# Buspirate_Main.net
KiCad netlist of a schematic drawn in EasyEDA Pro
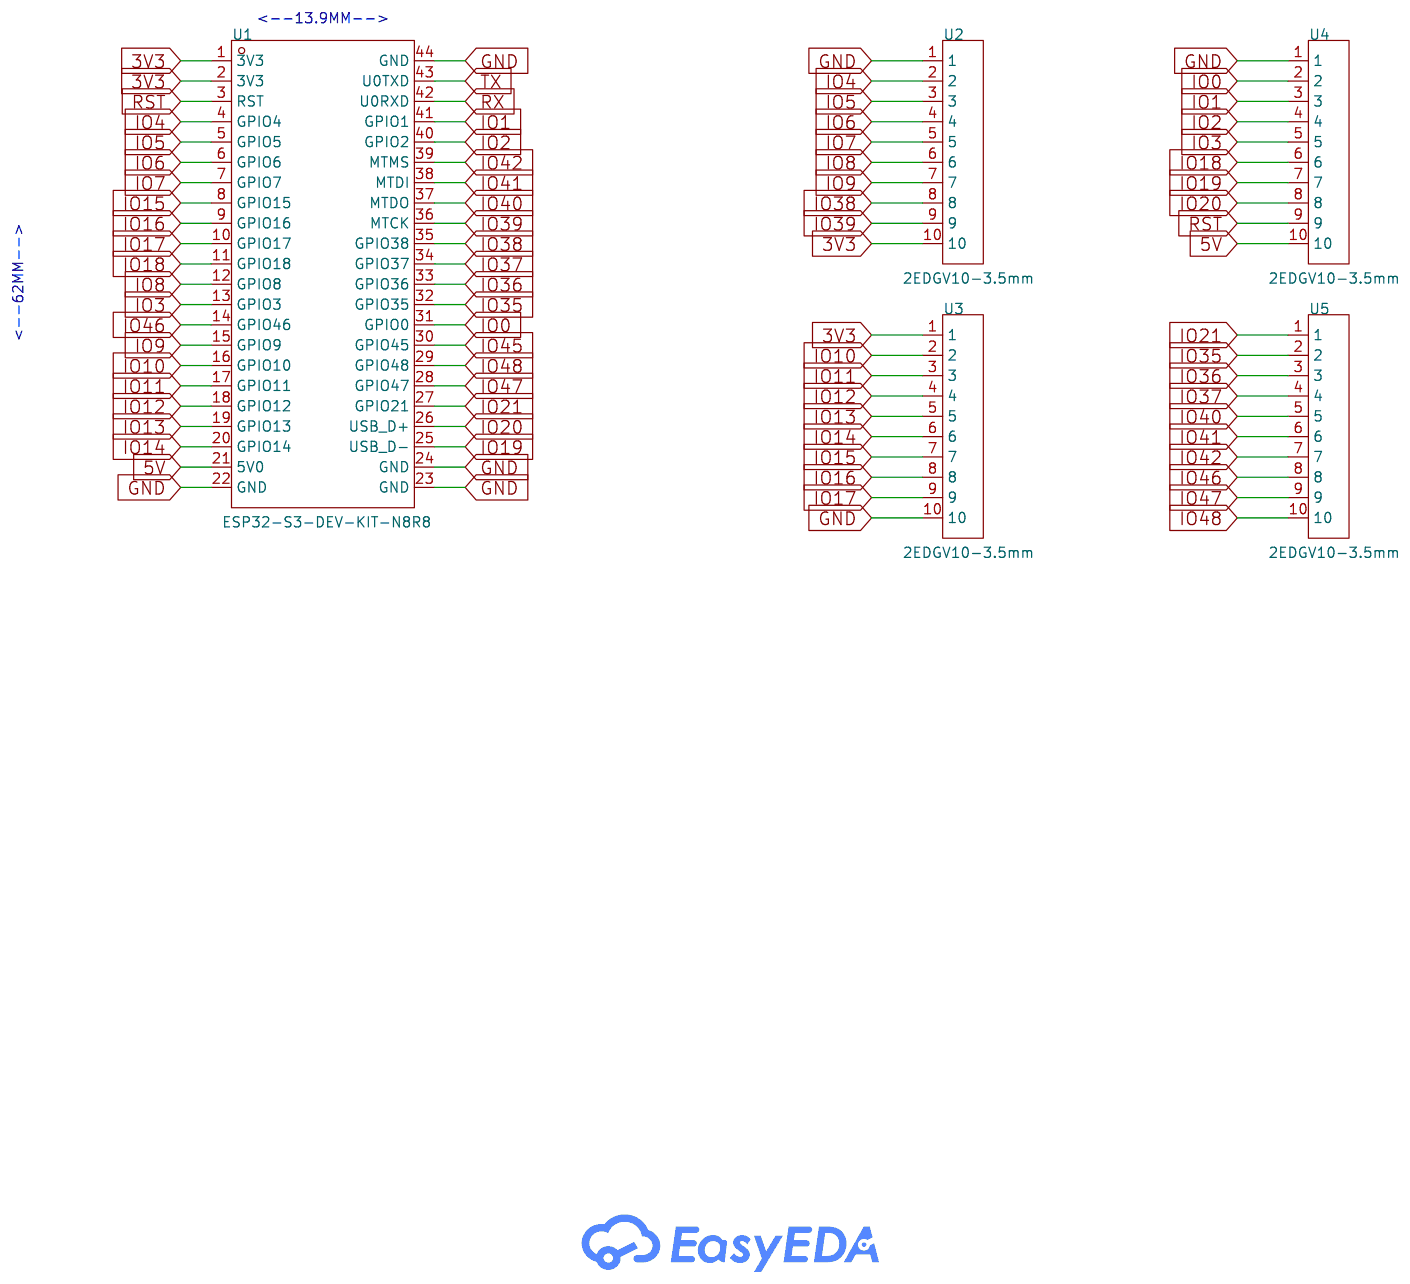
[diagram p0: schematic sheet]

(export (version "E")
  (design (tool "Eeschema 10.0.6"))
  (components
    (comp (ref "U1")
      (value "ESP32-S3-DEV-KIT-N8R8")
      (footprint "easyedapro:COMM-TH_L63.3-W25.4-P2.54-LS22.86")
      (libsource (lib "easyedapro") (part "ESP32-S3-DEV-KIT-N8R8"))
    )
    (comp (ref "U2")
      (value "2EDGV10-3.5mm")
      (footprint "easyedapro:CONN-TH_10P-P3.50")
      (libsource (lib "easyedapro") (part "CONN-TH_10P-P3.50"))
    )
    (comp (ref "U3")
      (value "2EDGV10-3.5mm")
      (footprint "easyedapro:CONN-TH_10P-P3.50")
      (libsource (lib "easyedapro") (part "CONN-TH_10P-P3.50"))
    )
    (comp (ref "U4")
      (value "2EDGV10-3.5mm")
      (footprint "easyedapro:CONN-TH_10P-P3.50")
      (libsource (lib "easyedapro") (part "CONN-TH_10P-P3.50"))
    )
    (comp (ref "U5")
      (value "2EDGV10-3.5mm")
      (footprint "easyedapro:CONN-TH_10P-P3.50")
      (libsource (lib "easyedapro") (part "CONN-TH_10P-P3.50"))
    )
  )
  (nets
    (net (code "1") (name "3V3") (class "Default")
      (node (ref "U1") (pin "1") (pinfunction "3V3_1") (pintype "unspecified"))
      (node (ref "U1") (pin "2") (pinfunction "3V3_2") (pintype "unspecified"))
      (node (ref "U2") (pin "10") (pinfunction "10_10") (pintype "unspecified"))
      (node (ref "U3") (pin "1") (pinfunction "1_1") (pintype "unspecified"))
    )
    (net (code "2") (name "5V") (class "Default")
      (node (ref "U1") (pin "21") (pinfunction "5V0_21") (pintype "unspecified"))
      (node (ref "U4") (pin "10") (pinfunction "10_10") (pintype "unspecified"))
    )
    (net (code "3") (name "GND") (class "Default")
      (node (ref "U1") (pin "22") (pinfunction "GND_22") (pintype "unspecified"))
      (node (ref "U1") (pin "23") (pinfunction "GND_23") (pintype "unspecified"))
      (node (ref "U1") (pin "24") (pinfunction "GND_24") (pintype "unspecified"))
      (node (ref "U1") (pin "44") (pinfunction "GND_44") (pintype "unspecified"))
      (node (ref "U2") (pin "1") (pinfunction "1_1") (pintype "unspecified"))
      (node (ref "U3") (pin "10") (pinfunction "10_10") (pintype "unspecified"))
      (node (ref "U4") (pin "1") (pinfunction "1_1") (pintype "unspecified"))
    )
    (net (code "4") (name "IO0") (class "Default")
      (node (ref "U1") (pin "31") (pinfunction "GPIO0_31") (pintype "unspecified"))
      (node (ref "U4") (pin "2") (pinfunction "2_2") (pintype "unspecified"))
    )
    (net (code "5") (name "IO1") (class "Default")
      (node (ref "U1") (pin "41") (pinfunction "GPIO1_41") (pintype "unspecified"))
      (node (ref "U4") (pin "3") (pinfunction "3_3") (pintype "unspecified"))
    )
    (net (code "6") (name "IO2") (class "Default")
      (node (ref "U1") (pin "40") (pinfunction "GPIO2_40") (pintype "unspecified"))
      (node (ref "U4") (pin "4") (pinfunction "4_4") (pintype "unspecified"))
    )
    (net (code "7") (name "IO3") (class "Default")
      (node (ref "U1") (pin "13") (pinfunction "GPIO3_13") (pintype "unspecified"))
      (node (ref "U4") (pin "5") (pinfunction "5_5") (pintype "unspecified"))
    )
    (net (code "8") (name "IO4") (class "Default")
      (node (ref "U1") (pin "4") (pinfunction "GPIO4_4") (pintype "unspecified"))
      (node (ref "U2") (pin "2") (pinfunction "2_2") (pintype "unspecified"))
    )
    (net (code "9") (name "IO5") (class "Default")
      (node (ref "U1") (pin "5") (pinfunction "GPIO5_5") (pintype "unspecified"))
      (node (ref "U2") (pin "3") (pinfunction "3_3") (pintype "unspecified"))
    )
    (net (code "10") (name "IO6") (class "Default")
      (node (ref "U1") (pin "6") (pinfunction "GPIO6_6") (pintype "unspecified"))
      (node (ref "U2") (pin "4") (pinfunction "4_4") (pintype "unspecified"))
    )
    (net (code "11") (name "IO7") (class "Default")
      (node (ref "U1") (pin "7") (pinfunction "GPIO7_7") (pintype "unspecified"))
      (node (ref "U2") (pin "5") (pinfunction "5_5") (pintype "unspecified"))
    )
    (net (code "12") (name "IO8") (class "Default")
      (node (ref "U1") (pin "12") (pinfunction "GPIO8_12") (pintype "unspecified"))
      (node (ref "U2") (pin "6") (pinfunction "6_6") (pintype "unspecified"))
    )
    (net (code "13") (name "IO9") (class "Default")
      (node (ref "U1") (pin "15") (pinfunction "GPIO9_15") (pintype "unspecified"))
      (node (ref "U2") (pin "7") (pinfunction "7_7") (pintype "unspecified"))
    )
    (net (code "14") (name "IO10") (class "Default")
      (node (ref "U1") (pin "16") (pinfunction "GPIO10_16") (pintype "unspecified"))
      (node (ref "U3") (pin "2") (pinfunction "2_2") (pintype "unspecified"))
    )
    (net (code "15") (name "IO11") (class "Default")
      (node (ref "U1") (pin "17") (pinfunction "GPIO11_17") (pintype "unspecified"))
      (node (ref "U3") (pin "3") (pinfunction "3_3") (pintype "unspecified"))
    )
    (net (code "16") (name "IO12") (class "Default")
      (node (ref "U1") (pin "18") (pinfunction "GPIO12_18") (pintype "unspecified"))
      (node (ref "U3") (pin "4") (pinfunction "4_4") (pintype "unspecified"))
    )
    (net (code "17") (name "IO13") (class "Default")
      (node (ref "U1") (pin "19") (pinfunction "GPIO13_19") (pintype "unspecified"))
      (node (ref "U3") (pin "5") (pinfunction "5_5") (pintype "unspecified"))
    )
    (net (code "18") (name "IO14") (class "Default")
      (node (ref "U1") (pin "20") (pinfunction "GPIO14_20") (pintype "unspecified"))
      (node (ref "U3") (pin "6") (pinfunction "6_6") (pintype "unspecified"))
    )
    (net (code "19") (name "IO15") (class "Default")
      (node (ref "U1") (pin "8") (pinfunction "GPIO15_8") (pintype "unspecified"))
      (node (ref "U3") (pin "7") (pinfunction "7_7") (pintype "unspecified"))
    )
    (net (code "20") (name "IO16") (class "Default")
      (node (ref "U1") (pin "9") (pinfunction "GPIO16_9") (pintype "unspecified"))
      (node (ref "U3") (pin "8") (pinfunction "8_8") (pintype "unspecified"))
    )
    (net (code "21") (name "IO17") (class "Default")
      (node (ref "U1") (pin "10") (pinfunction "GPIO17_10") (pintype "unspecified"))
      (node (ref "U3") (pin "9") (pinfunction "9_9") (pintype "unspecified"))
    )
    (net (code "22") (name "IO18") (class "Default")
      (node (ref "U1") (pin "11") (pinfunction "GPIO18_11") (pintype "unspecified"))
      (node (ref "U4") (pin "6") (pinfunction "6_6") (pintype "unspecified"))
    )
    (net (code "23") (name "IO19") (class "Default")
      (node (ref "U1") (pin "25") (pinfunction "USB_D-_25") (pintype "unspecified"))
      (node (ref "U4") (pin "7") (pinfunction "7_7") (pintype "unspecified"))
    )
    (net (code "24") (name "IO20") (class "Default")
      (node (ref "U1") (pin "26") (pinfunction "USB_D+_26") (pintype "unspecified"))
      (node (ref "U4") (pin "8") (pinfunction "8_8") (pintype "unspecified"))
    )
    (net (code "25") (name "IO21") (class "Default")
      (node (ref "U1") (pin "27") (pinfunction "GPIO21_27") (pintype "unspecified"))
      (node (ref "U5") (pin "1") (pinfunction "1_1") (pintype "unspecified"))
    )
    (net (code "26") (name "IO35") (class "Default")
      (node (ref "U1") (pin "32") (pinfunction "GPIO35_32") (pintype "unspecified"))
      (node (ref "U5") (pin "2") (pinfunction "2_2") (pintype "unspecified"))
    )
    (net (code "27") (name "IO36") (class "Default")
      (node (ref "U1") (pin "33") (pinfunction "GPIO36_33") (pintype "unspecified"))
      (node (ref "U5") (pin "3") (pinfunction "3_3") (pintype "unspecified"))
    )
    (net (code "28") (name "IO37") (class "Default")
      (node (ref "U1") (pin "34") (pinfunction "GPIO37_34") (pintype "unspecified"))
      (node (ref "U5") (pin "4") (pinfunction "4_4") (pintype "unspecified"))
    )
    (net (code "29") (name "IO38") (class "Default")
      (node (ref "U1") (pin "35") (pinfunction "GPIO38_35") (pintype "unspecified"))
      (node (ref "U2") (pin "8") (pinfunction "8_8") (pintype "unspecified"))
    )
    (net (code "30") (name "IO39") (class "Default")
      (node (ref "U1") (pin "36") (pinfunction "MTCK_36") (pintype "unspecified"))
      (node (ref "U2") (pin "9") (pinfunction "9_9") (pintype "unspecified"))
    )
    (net (code "31") (name "IO40") (class "Default")
      (node (ref "U1") (pin "37") (pinfunction "MTDO_37") (pintype "unspecified"))
      (node (ref "U5") (pin "5") (pinfunction "5_5") (pintype "unspecified"))
    )
    (net (code "32") (name "IO41") (class "Default")
      (node (ref "U1") (pin "38") (pinfunction "MTDI_38") (pintype "unspecified"))
      (node (ref "U5") (pin "6") (pinfunction "6_6") (pintype "unspecified"))
    )
    (net (code "33") (name "IO42") (class "Default")
      (node (ref "U1") (pin "39") (pinfunction "MTMS_39") (pintype "unspecified"))
      (node (ref "U5") (pin "7") (pinfunction "7_7") (pintype "unspecified"))
    )
    (net (code "34") (name "IO45") (class "Default")
      (node (ref "U1") (pin "30") (pinfunction "GPIO45_30") (pintype "unspecified"))
    )
    (net (code "35") (name "IO46") (class "Default")
      (node (ref "U1") (pin "14") (pinfunction "GPIO46_14") (pintype "unspecified"))
      (node (ref "U5") (pin "8") (pinfunction "8_8") (pintype "unspecified"))
    )
    (net (code "36") (name "IO47") (class "Default")
      (node (ref "U1") (pin "28") (pinfunction "GPIO47_28") (pintype "unspecified"))
      (node (ref "U5") (pin "9") (pinfunction "9_9") (pintype "unspecified"))
    )
    (net (code "37") (name "IO48") (class "Default")
      (node (ref "U1") (pin "29") (pinfunction "GPIO48_29") (pintype "unspecified"))
      (node (ref "U5") (pin "10") (pinfunction "10_10") (pintype "unspecified"))
    )
    (net (code "38") (name "RST") (class "Default")
      (node (ref "U1") (pin "3") (pinfunction "RST_3") (pintype "unspecified"))
      (node (ref "U4") (pin "9") (pinfunction "9_9") (pintype "unspecified"))
    )
    (net (code "39") (name "RX") (class "Default")
      (node (ref "U1") (pin "42") (pinfunction "U0RXD_42") (pintype "unspecified"))
    )
    (net (code "40") (name "TX") (class "Default")
      (node (ref "U1") (pin "43") (pinfunction "U0TXD_43") (pintype "unspecified"))
    )
  )
)
